# PCB-BI8-2x1.net
KiCad netlist of a schematic drawn in EAGLE
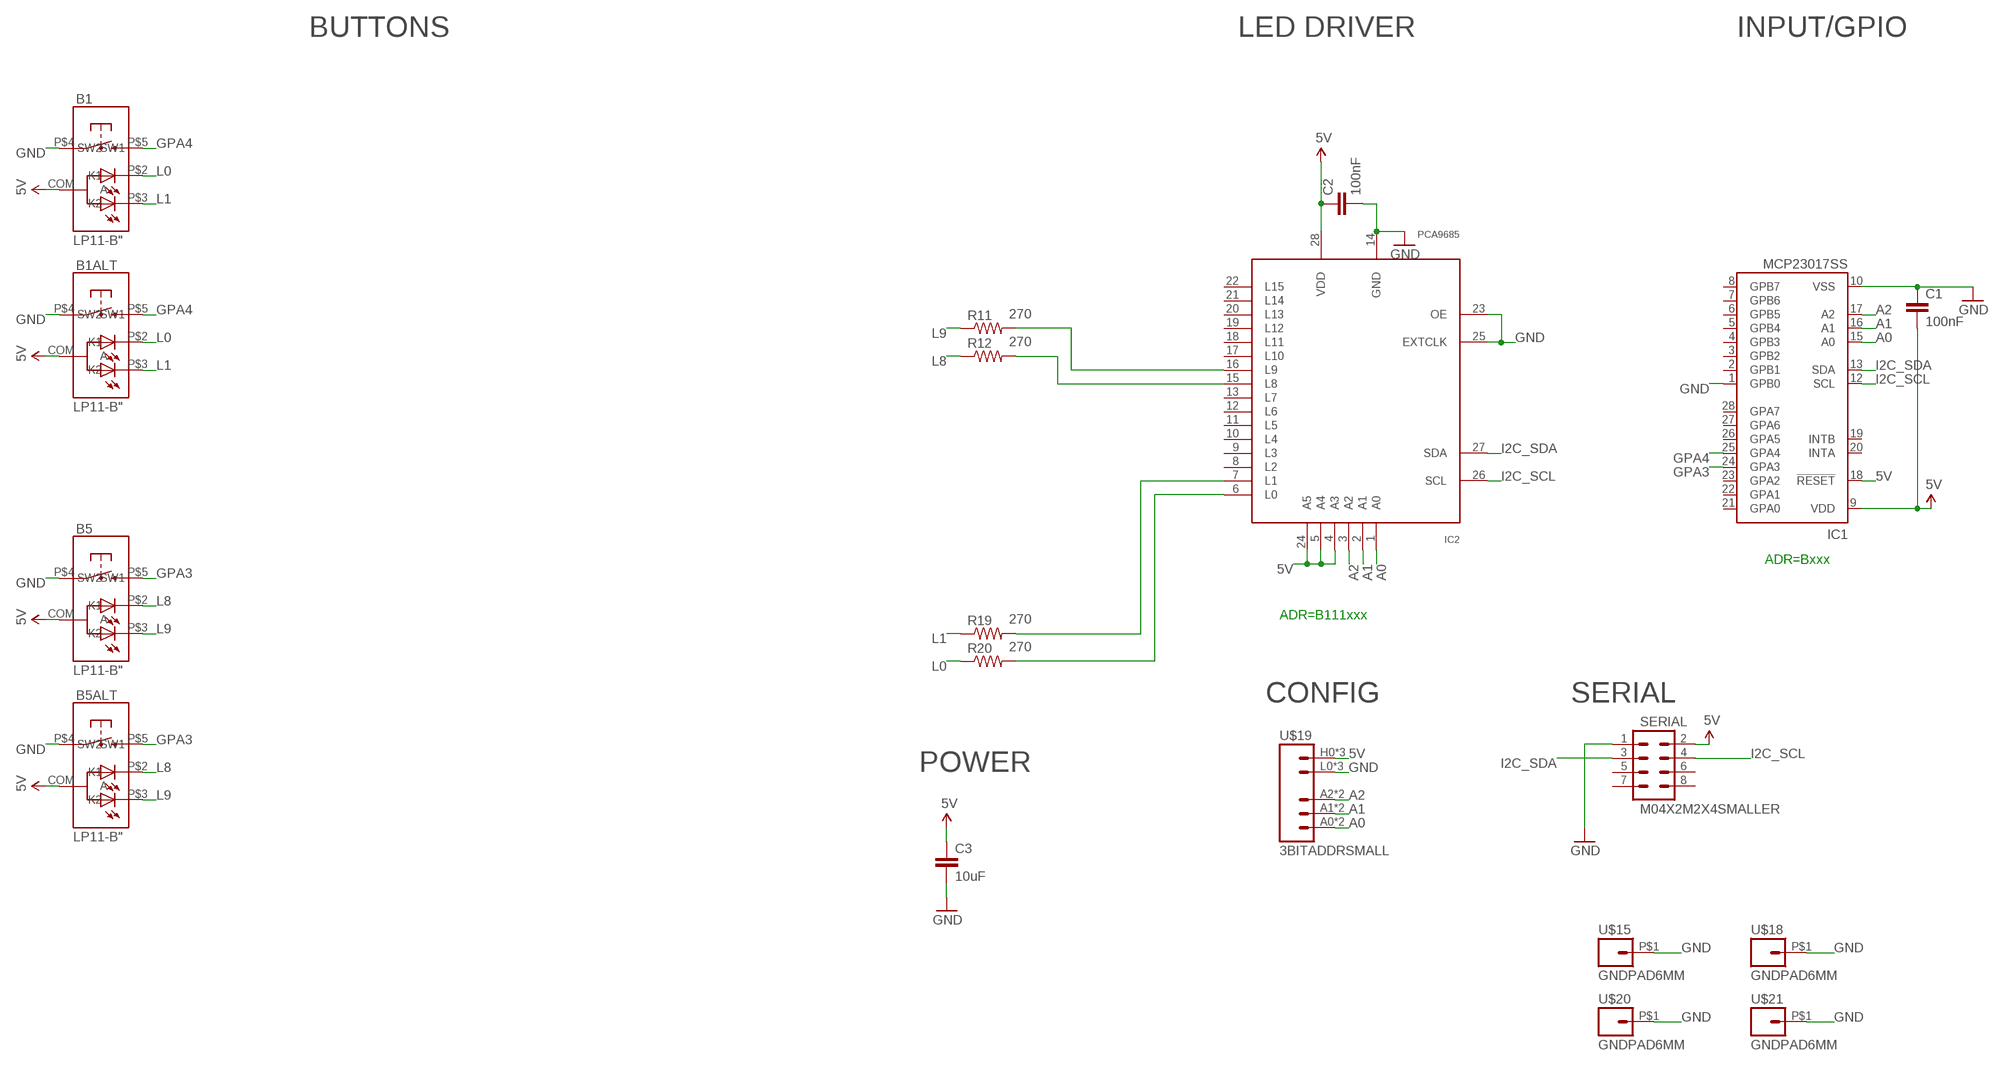
[diagram p0: schematic, sheet 1]

(export (version "E")
  (design (tool "Eeschema 10.0.6"))
  (components
    (comp (ref "B1")
      (value "LP11-B\"")
      (footprint "eagle-import:LP11")
      (libsource (lib "eagle-import") (part "LP11-B{dblquote}"))
    )
    (comp (ref "B1ALT")
      (value "LP11-B\"")
      (footprint "eagle-import:LP11")
      (libsource (lib "eagle-import") (part "LP11-B{dblquote}"))
    )
    (comp (ref "B5")
      (value "LP11-B\"")
      (footprint "eagle-import:LP11")
      (libsource (lib "eagle-import") (part "LP11-B{dblquote}"))
    )
    (comp (ref "B5ALT")
      (value "LP11-B\"")
      (footprint "eagle-import:LP11")
      (libsource (lib "eagle-import") (part "LP11-B{dblquote}"))
    )
    (comp (ref "C1")
      (value "100nF")
      (footprint "eagle-import:0603-CAP")
      (libsource (lib "eagle-import") (part "CAP0603-CAP"))
    )
    (comp (ref "C2")
      (value "100nF")
      (footprint "eagle-import:0603-CAP")
      (libsource (lib "eagle-import") (part "CAP0603-CAP"))
    )
    (comp (ref "C3")
      (value "10uF")
      (footprint "eagle-import:0805")
      (libsource (lib "eagle-import") (part "CAP0805"))
    )
    (comp (ref "IC1")
      (value "MCP23017SS")
      (footprint "eagle-import:SSOP28")
      (fields
        (field (name "MF") "MICROCHIP")
        (field (name "MPN") "MCP23017-E/SS")
        (field (name "MPN_1") "MCP23017-E/SS")
        (field (name "OC_FARNELL") "1467674")
        (field (name "OC_NEWARK") "31K2960")
      )
      (libsource (lib "eagle-import") (part "MCP23017SS"))
    )
    (comp (ref "IC2")
      (value "PCA9685")
      (footprint "eagle-import:TSSOP28")
      (libsource (lib "eagle-import") (part "PCA9685"))
    )
    (comp (ref "R11")
      (value "270")
      (footprint "eagle-import:0603-RES")
      (libsource (lib "eagle-import") (part "RESISTOR0603-RES"))
    )
    (comp (ref "R12")
      (value "270")
      (footprint "eagle-import:0603-RES")
      (libsource (lib "eagle-import") (part "RESISTOR0603-RES"))
    )
    (comp (ref "R19")
      (value "270")
      (footprint "eagle-import:0603-RES")
      (libsource (lib "eagle-import") (part "RESISTOR0603-RES"))
    )
    (comp (ref "R20")
      (value "270")
      (footprint "eagle-import:0603-RES")
      (libsource (lib "eagle-import") (part "RESISTOR0603-RES"))
    )
    (comp (ref "SERIAL")
      (value "M04X2M2X4SMALLER")
      (footprint "eagle-import:M2X4SMALLER")
      (libsource (lib "eagle-import") (part "M04X2M2X4SMALLER"))
    )
    (comp (ref "U$15")
      (value "GNDPAD6MM")
      (footprint "eagle-import:3.2MMPAD6MM")
      (libsource (lib "eagle-import") (part "GNDPAD6MM"))
    )
    (comp (ref "U$18")
      (value "GNDPAD6MM")
      (footprint "eagle-import:3.2MMPAD6MM")
      (libsource (lib "eagle-import") (part "GNDPAD6MM"))
    )
    (comp (ref "U$19")
      (value "3BITADDRSMALL")
      (footprint "eagle-import:3BITADDR_SMALL")
      (libsource (lib "eagle-import") (part "3BITADDRSMALL"))
    )
    (comp (ref "U$20")
      (value "GNDPAD6MM")
      (footprint "eagle-import:3.2MMPAD6MM")
      (libsource (lib "eagle-import") (part "GNDPAD6MM"))
    )
    (comp (ref "U$21")
      (value "GNDPAD6MM")
      (footprint "eagle-import:3.2MMPAD6MM")
      (libsource (lib "eagle-import") (part "GNDPAD6MM"))
    )
  )
  (nets
    (net (code "1") (name "5V") (class "Default")
      (node (ref "B1") (pin "COM") (pinfunction "A_COM") (pintype "bidirectional"))
      (node (ref "B1ALT") (pin "COM") (pinfunction "A_COM") (pintype "bidirectional"))
      (node (ref "B5") (pin "COM") (pinfunction "A_COM") (pintype "bidirectional"))
      (node (ref "B5ALT") (pin "COM") (pinfunction "A_COM") (pintype "bidirectional"))
      (node (ref "C1") (pin "2") (pinfunction "2_2") (pintype "passive"))
      (node (ref "C2") (pin "1") (pinfunction "1_1") (pintype "passive"))
      (node (ref "C3") (pin "1") (pinfunction "1_1") (pintype "passive"))
      (node (ref "IC1") (pin "18") (pinfunction "~{RESET}_18") (pintype "input"))
      (node (ref "IC1") (pin "9") (pinfunction "VDD_9") (pintype "power_in"))
      (node (ref "IC2") (pin "24") (pinfunction "A5_24") (pintype "input"))
      (node (ref "IC2") (pin "28") (pinfunction "VDD_28") (pintype "power_in"))
      (node (ref "IC2") (pin "4") (pinfunction "A3_4") (pintype "input"))
      (node (ref "IC2") (pin "5") (pinfunction "A4_5") (pintype "input"))
      (node (ref "SERIAL") (pin "2") (pinfunction "2_2") (pintype "passive"))
      (node (ref "U$19") (pin "H0") (pinfunction "VCC_H0") (pintype "passive"))
      (node (ref "U$19") (pin "H1") (pinfunction "VCC_H1") (pintype "passive"))
      (node (ref "U$19") (pin "H2") (pinfunction "VCC_H2") (pintype "passive"))
    )
    (net (code "2") (name "A0") (class "Default")
      (node (ref "IC1") (pin "15") (pinfunction "A0_15") (pintype "input"))
      (node (ref "IC2") (pin "1") (pinfunction "A0_1") (pintype "input"))
      (node (ref "U$19") (pin "A0") (pinfunction "A0_A0") (pintype "passive"))
      (node (ref "U$19") (pin "AS0") (pinfunction "A0_AS0") (pintype "passive"))
    )
    (net (code "3") (name "A1") (class "Default")
      (node (ref "IC1") (pin "16") (pinfunction "A1_16") (pintype "input"))
      (node (ref "IC2") (pin "2") (pinfunction "A1_2") (pintype "input"))
      (node (ref "U$19") (pin "A1") (pinfunction "A1_A1") (pintype "passive"))
      (node (ref "U$19") (pin "AS1") (pinfunction "A1_AS1") (pintype "passive"))
    )
    (net (code "4") (name "A2") (class "Default")
      (node (ref "IC1") (pin "17") (pinfunction "A2_17") (pintype "input"))
      (node (ref "IC2") (pin "3") (pinfunction "A2_3") (pintype "input"))
      (node (ref "U$19") (pin "A2") (pinfunction "A2_A2") (pintype "passive"))
      (node (ref "U$19") (pin "AS2") (pinfunction "A2_AS2") (pintype "passive"))
    )
    (net (code "5") (name "GND") (class "Default")
      (node (ref "B1") (pin "P$4") (pinfunction "SW1_P$4") (pintype "bidirectional"))
      (node (ref "B1ALT") (pin "P$4") (pinfunction "SW1_P$4") (pintype "bidirectional"))
      (node (ref "B5") (pin "P$4") (pinfunction "SW1_P$4") (pintype "bidirectional"))
      (node (ref "B5ALT") (pin "P$4") (pinfunction "SW1_P$4") (pintype "bidirectional"))
      (node (ref "C1") (pin "1") (pinfunction "1_1") (pintype "passive"))
      (node (ref "C2") (pin "2") (pinfunction "2_2") (pintype "passive"))
      (node (ref "C3") (pin "2") (pinfunction "2_2") (pintype "passive"))
      (node (ref "IC1") (pin "1") (pinfunction "GPB0_1") (pintype "bidirectional"))
      (node (ref "IC1") (pin "10") (pinfunction "VSS_10") (pintype "power_in"))
      (node (ref "IC2") (pin "14") (pinfunction "GND_14") (pintype "power_in"))
      (node (ref "IC2") (pin "23") (pinfunction "OE_23") (pintype "input"))
      (node (ref "IC2") (pin "25") (pinfunction "EXTCLK_25") (pintype "input"))
      (node (ref "SERIAL") (pin "1") (pinfunction "1_1") (pintype "passive"))
      (node (ref "U$15") (pin "P$1") (pinfunction "1_P$1") (pintype "passive"))
      (node (ref "U$18") (pin "P$1") (pinfunction "1_P$1") (pintype "passive"))
      (node (ref "U$19") (pin "L0") (pinfunction "GND_L0") (pintype "passive"))
      (node (ref "U$19") (pin "L1") (pinfunction "GND_L1") (pintype "passive"))
      (node (ref "U$19") (pin "L2") (pinfunction "GND_L2") (pintype "passive"))
      (node (ref "U$20") (pin "P$1") (pinfunction "1_P$1") (pintype "passive"))
      (node (ref "U$21") (pin "P$1") (pinfunction "1_P$1") (pintype "passive"))
    )
    (net (code "6") (name "GPA3") (class "Default")
      (node (ref "B5") (pin "P$5") (pinfunction "SW2_P$5") (pintype "bidirectional"))
      (node (ref "B5ALT") (pin "P$5") (pinfunction "SW2_P$5") (pintype "bidirectional"))
      (node (ref "IC1") (pin "24") (pinfunction "GPA3_24") (pintype "bidirectional"))
    )
    (net (code "7") (name "GPA4") (class "Default")
      (node (ref "B1") (pin "P$5") (pinfunction "SW2_P$5") (pintype "bidirectional"))
      (node (ref "B1ALT") (pin "P$5") (pinfunction "SW2_P$5") (pintype "bidirectional"))
      (node (ref "IC1") (pin "25") (pinfunction "GPA4_25") (pintype "bidirectional"))
    )
    (net (code "8") (name "I2C_SCL") (class "Default")
      (node (ref "IC1") (pin "12") (pinfunction "SCL_12") (pintype "input"))
      (node (ref "IC2") (pin "26") (pinfunction "SCL_26") (pintype "input"))
      (node (ref "SERIAL") (pin "4") (pinfunction "4_4") (pintype "passive"))
    )
    (net (code "9") (name "I2C_SDA") (class "Default")
      (node (ref "IC1") (pin "13") (pinfunction "SDA_13") (pintype "bidirectional"))
      (node (ref "IC2") (pin "27") (pinfunction "SDA_27") (pintype "input"))
      (node (ref "SERIAL") (pin "3") (pinfunction "3_3") (pintype "passive"))
    )
    (net (code "10") (name "L0") (class "Default")
      (node (ref "B1") (pin "P$2") (pinfunction "K1_P$2") (pintype "bidirectional"))
      (node (ref "B1ALT") (pin "P$2") (pinfunction "K1_P$2") (pintype "bidirectional"))
      (node (ref "R20") (pin "1") (pinfunction "1_1") (pintype "passive"))
    )
    (net (code "11") (name "L1") (class "Default")
      (node (ref "B1") (pin "P$3") (pinfunction "K2_P$3") (pintype "bidirectional"))
      (node (ref "B1ALT") (pin "P$3") (pinfunction "K2_P$3") (pintype "bidirectional"))
      (node (ref "R19") (pin "1") (pinfunction "1_1") (pintype "passive"))
    )
    (net (code "12") (name "L8") (class "Default")
      (node (ref "B5") (pin "P$2") (pinfunction "K1_P$2") (pintype "bidirectional"))
      (node (ref "B5ALT") (pin "P$2") (pinfunction "K1_P$2") (pintype "bidirectional"))
      (node (ref "R12") (pin "1") (pinfunction "1_1") (pintype "passive"))
    )
    (net (code "13") (name "L9") (class "Default")
      (node (ref "B5") (pin "P$3") (pinfunction "K2_P$3") (pintype "bidirectional"))
      (node (ref "B5ALT") (pin "P$3") (pinfunction "K2_P$3") (pintype "bidirectional"))
      (node (ref "R11") (pin "1") (pinfunction "1_1") (pintype "passive"))
    )
    (net (code "14") (name "Net-(IC2-L0)") (class "Default")
      (node (ref "IC2") (pin "6") (pinfunction "L0_6") (pintype "output"))
      (node (ref "R20") (pin "2") (pinfunction "2_2") (pintype "passive"))
    )
    (net (code "15") (name "Net-(IC2-L1)") (class "Default")
      (node (ref "IC2") (pin "7") (pinfunction "L1_7") (pintype "output"))
      (node (ref "R19") (pin "2") (pinfunction "2_2") (pintype "passive"))
    )
    (net (code "16") (name "Net-(IC2-L8)") (class "Default")
      (node (ref "IC2") (pin "15") (pinfunction "L8_15") (pintype "output"))
      (node (ref "R12") (pin "2") (pinfunction "2_2") (pintype "passive"))
    )
    (net (code "17") (name "Net-(IC2-L9)") (class "Default")
      (node (ref "IC2") (pin "16") (pinfunction "L9_16") (pintype "output"))
      (node (ref "R11") (pin "2") (pinfunction "2_2") (pintype "passive"))
    )
    (net (code "18") (name "unconnected-(IC1-GPA0-Pad21)") (class "Default")
      (node (ref "IC1") (pin "21") (pinfunction "GPA0_21") (pintype "bidirectional"))
    )
    (net (code "19") (name "unconnected-(IC1-GPA1-Pad22)") (class "Default")
      (node (ref "IC1") (pin "22") (pinfunction "GPA1_22") (pintype "bidirectional"))
    )
    (net (code "20") (name "unconnected-(IC1-GPA2-Pad23)") (class "Default")
      (node (ref "IC1") (pin "23") (pinfunction "GPA2_23") (pintype "bidirectional"))
    )
    (net (code "21") (name "unconnected-(IC1-GPA5-Pad26)") (class "Default")
      (node (ref "IC1") (pin "26") (pinfunction "GPA5_26") (pintype "bidirectional"))
    )
    (net (code "22") (name "unconnected-(IC1-GPA6-Pad27)") (class "Default")
      (node (ref "IC1") (pin "27") (pinfunction "GPA6_27") (pintype "bidirectional"))
    )
    (net (code "23") (name "unconnected-(IC1-GPA7-Pad28)") (class "Default")
      (node (ref "IC1") (pin "28") (pinfunction "GPA7_28") (pintype "bidirectional"))
    )
    (net (code "24") (name "unconnected-(IC1-GPB1-Pad2)") (class "Default")
      (node (ref "IC1") (pin "2") (pinfunction "GPB1_2") (pintype "bidirectional"))
    )
    (net (code "25") (name "unconnected-(IC1-GPB2-Pad3)") (class "Default")
      (node (ref "IC1") (pin "3") (pinfunction "GPB2_3") (pintype "bidirectional"))
    )
    (net (code "26") (name "unconnected-(IC1-GPB3-Pad4)") (class "Default")
      (node (ref "IC1") (pin "4") (pinfunction "GPB3_4") (pintype "bidirectional"))
    )
    (net (code "27") (name "unconnected-(IC1-GPB4-Pad5)") (class "Default")
      (node (ref "IC1") (pin "5") (pinfunction "GPB4_5") (pintype "bidirectional"))
    )
    (net (code "28") (name "unconnected-(IC1-GPB5-Pad6)") (class "Default")
      (node (ref "IC1") (pin "6") (pinfunction "GPB5_6") (pintype "bidirectional"))
    )
    (net (code "29") (name "unconnected-(IC1-GPB6-Pad7)") (class "Default")
      (node (ref "IC1") (pin "7") (pinfunction "GPB6_7") (pintype "bidirectional"))
    )
    (net (code "30") (name "unconnected-(IC1-GPB7-Pad8)") (class "Default")
      (node (ref "IC1") (pin "8") (pinfunction "GPB7_8") (pintype "bidirectional"))
    )
    (net (code "31") (name "unconnected-(IC1-INTA-Pad20)") (class "Default")
      (node (ref "IC1") (pin "20") (pinfunction "INTA_20") (pintype "output"))
    )
    (net (code "32") (name "unconnected-(IC1-INTB-Pad19)") (class "Default")
      (node (ref "IC1") (pin "19") (pinfunction "INTB_19") (pintype "output"))
    )
    (net (code "33") (name "unconnected-(IC2-L2-Pad8)") (class "Default")
      (node (ref "IC2") (pin "8") (pinfunction "L2_8") (pintype "output"))
    )
    (net (code "34") (name "unconnected-(IC2-L3-Pad9)") (class "Default")
      (node (ref "IC2") (pin "9") (pinfunction "L3_9") (pintype "output"))
    )
    (net (code "35") (name "unconnected-(IC2-L4-Pad10)") (class "Default")
      (node (ref "IC2") (pin "10") (pinfunction "L4_10") (pintype "output"))
    )
    (net (code "36") (name "unconnected-(IC2-L5-Pad11)") (class "Default")
      (node (ref "IC2") (pin "11") (pinfunction "L5_11") (pintype "output"))
    )
    (net (code "37") (name "unconnected-(IC2-L6-Pad12)") (class "Default")
      (node (ref "IC2") (pin "12") (pinfunction "L6_12") (pintype "output"))
    )
    (net (code "38") (name "unconnected-(IC2-L7-Pad13)") (class "Default")
      (node (ref "IC2") (pin "13") (pinfunction "L7_13") (pintype "output"))
    )
    (net (code "39") (name "unconnected-(IC2-L10-Pad17)") (class "Default")
      (node (ref "IC2") (pin "17") (pinfunction "L10_17") (pintype "output"))
    )
    (net (code "40") (name "unconnected-(IC2-L11-Pad18)") (class "Default")
      (node (ref "IC2") (pin "18") (pinfunction "L11_18") (pintype "output"))
    )
    (net (code "41") (name "unconnected-(IC2-L12-Pad19)") (class "Default")
      (node (ref "IC2") (pin "19") (pinfunction "L12_19") (pintype "output"))
    )
    (net (code "42") (name "unconnected-(IC2-L13-Pad20)") (class "Default")
      (node (ref "IC2") (pin "20") (pinfunction "L13_20") (pintype "output"))
    )
    (net (code "43") (name "unconnected-(IC2-L14-Pad21)") (class "Default")
      (node (ref "IC2") (pin "21") (pinfunction "L14_21") (pintype "output"))
    )
    (net (code "44") (name "unconnected-(IC2-L15-Pad22)") (class "Default")
      (node (ref "IC2") (pin "22") (pinfunction "L15_22") (pintype "output"))
    )
    (net (code "45") (name "unconnected-(SERIAL-Pad5)") (class "Default")
      (node (ref "SERIAL") (pin "5") (pinfunction "5_5") (pintype "passive"))
    )
    (net (code "46") (name "unconnected-(SERIAL-Pad6)") (class "Default")
      (node (ref "SERIAL") (pin "6") (pinfunction "6_6") (pintype "passive"))
    )
    (net (code "47") (name "unconnected-(SERIAL-Pad7)") (class "Default")
      (node (ref "SERIAL") (pin "7") (pinfunction "7_7") (pintype "passive"))
    )
    (net (code "48") (name "unconnected-(SERIAL-Pad8)") (class "Default")
      (node (ref "SERIAL") (pin "8") (pinfunction "8_8") (pintype "passive"))
    )
  )
)
